# eVV_Driver_TMC5130.net
KiCad netlist of a schematic drawn in Altium Designer
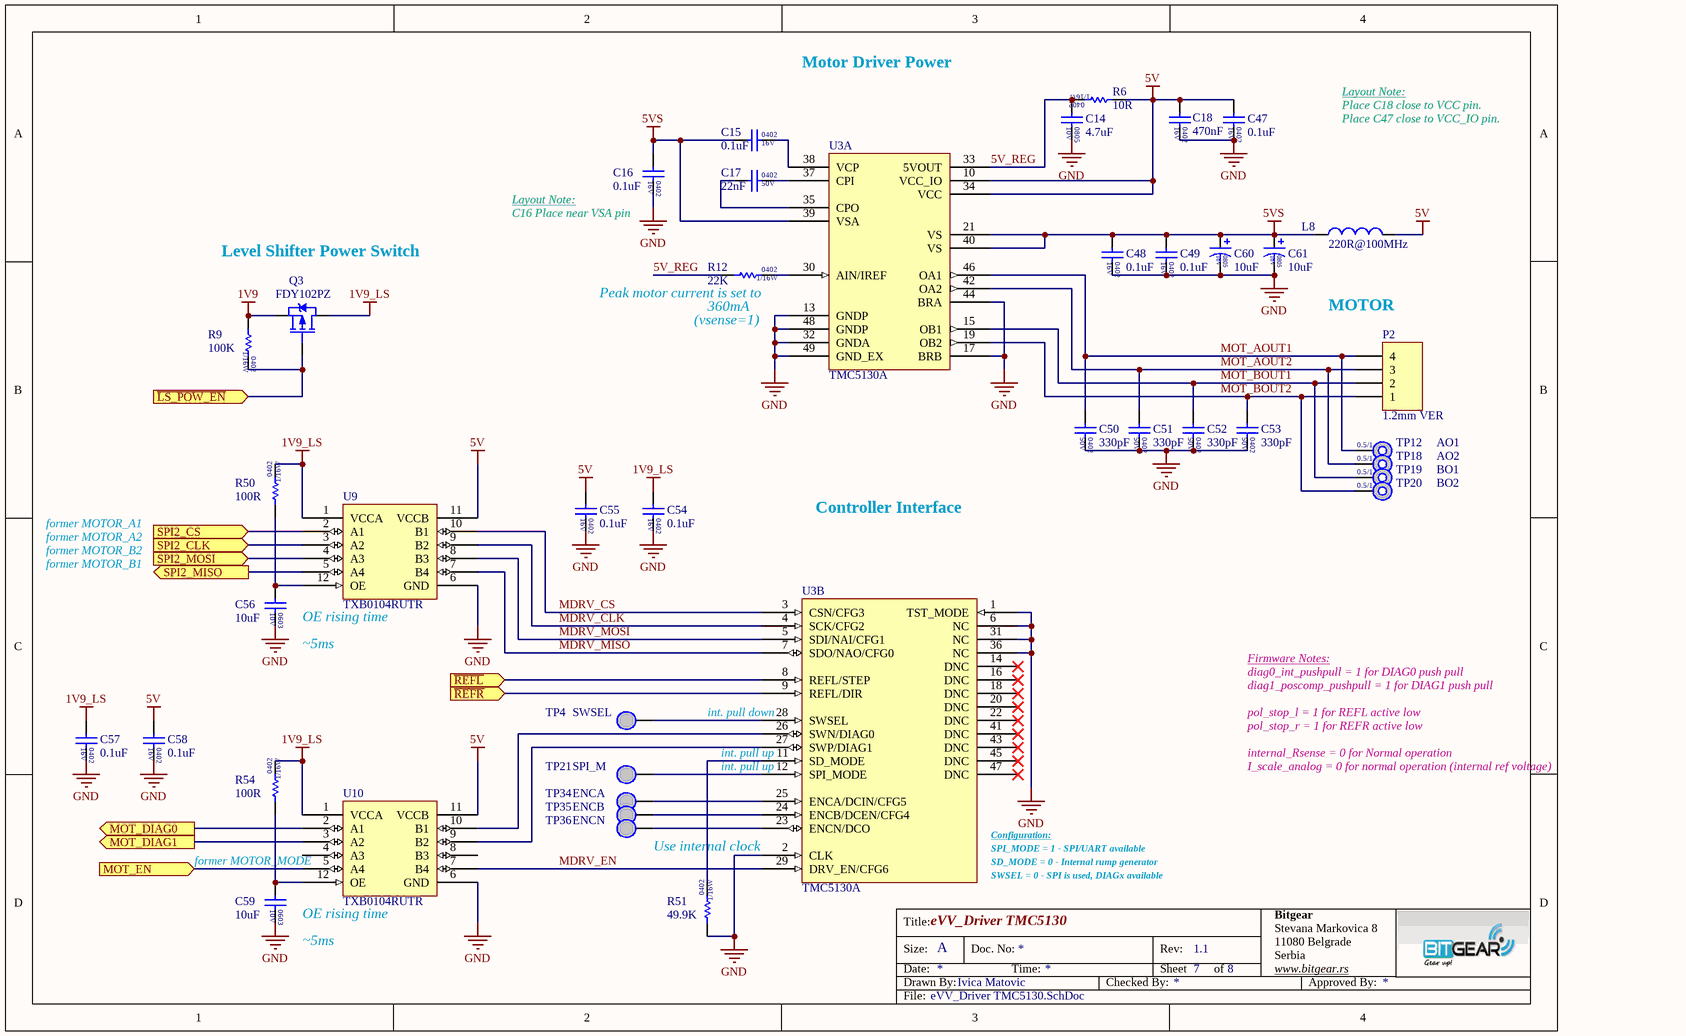
[diagram p0: eVV_Driver TMC5130.SchDoc]

(export (version "E")
  (design (tool "Eeschema 10.0.6"))
  (components
    (comp (ref "C14")
      (value "4.7uF")
      (footprint "CAPC2012X145N")
      (description "Capacitor Ceramic 4.7uF 2012 (0805) 10V X5R 10%")
      (fields (field (name "MANUFACTURER") "Samsung Electro-Mechanics America"))
      (libsource (lib "ecoVENTV") (part "Cap-2012 (0805) CER 4.7uF 10V X5R 10%"))
    )
    (comp (ref "C15")
      (value "0.1uF")
      (footprint "CAPC1005X60N")
      (description "CAP CER 0.1UF 0402 (1005) 16V X7R 10%")
      (fields (field (name "MANUFACTURER") "Murata Electronics North America"))
      (libsource (lib "ecoVENTV") (part "Cap-1005 (0402) CER 0.1UF 16V X7R 10%"))
    )
    (comp (ref "C16")
      (value "0.1uF")
      (footprint "CAPC1005X60N")
      (description "CAP CER 0.1UF 0402 (1005) 16V X7R 10%")
      (fields (field (name "MANUFACTURER") "Murata Electronics North America"))
      (libsource (lib "ecoVENTV") (part "Cap-1005 (0402) CER 0.1UF 16V X7R 10%"))
    )
    (comp (ref "C17")
      (value "22nF")
      (footprint "CAPC1005X60N")
      (description "Cap-1005 (0402) CER 22nF 50V X7R 10%")
      (fields (field (name "MANUFACTURER") "Murata Electronics North America"))
      (libsource (lib "ecoVENTV") (part "Cap-1005 (0402) CER 22nF 50V X7R 10%"))
    )
    (comp (ref "C18")
      (value "470nF")
      (footprint "CAPC1005X60N")
      (description "CAP Cer 470nF 0402 (1005) 16V X5R 10%")
      (fields (field (name "MANUFACTURER") "TDK"))
      (libsource (lib "ecoVENTV") (part "Cap-1005 (0402) Cer 470nF 16V X5R 10%"))
    )
    (comp (ref "C47")
      (value "0.1uF")
      (footprint "CAPC1005X60N")
      (description "CAP CER 0.1UF 0402 (1005) 16V X7R 10%")
      (fields (field (name "MANUFACTURER") "Murata Electronics North America"))
      (libsource (lib "ecoVENTV") (part "Cap-1005 (0402) CER 0.1UF 16V X7R 10%"))
    )
    (comp (ref "C48")
      (value "0.1uF")
      (footprint "CAPC1005X60N")
      (description "CAP CER 0.1UF 0402 (1005) 16V X7R 10%")
      (fields (field (name "MANUFACTURER") "Murata Electronics North America"))
      (libsource (lib "ecoVENTV") (part "Cap-1005 (0402) CER 0.1UF 16V X7R 10%"))
    )
    (comp (ref "C49")
      (value "0.1uF")
      (footprint "CAPC1005X60N")
      (description "CAP CER 0.1UF 0402 (1005) 16V X7R 10%")
      (fields (field (name "MANUFACTURER") "Murata Electronics North America"))
      (libsource (lib "ecoVENTV") (part "Cap-1005 (0402) CER 0.1UF 16V X7R 10%"))
    )
    (comp (ref "C50")
      (value "330pF")
      (footprint "CAPC1005X60N")
      (description "Cap-1005 (0402) CER 330pF 50V C0G 5%")
      (fields (field (name "MANUFACTURER") "Murata Electronics North America"))
      (libsource (lib "ecoVENTV") (part "Cap-1005 (0402) CER 330pF 50V C0G 5%"))
    )
    (comp (ref "C51")
      (value "330pF")
      (footprint "CAPC1005X60N")
      (description "Cap-1005 (0402) CER 330pF 50V C0G 5%")
      (fields (field (name "MANUFACTURER") "Murata Electronics North America"))
      (libsource (lib "ecoVENTV") (part "Cap-1005 (0402) CER 330pF 50V C0G 5%"))
    )
    (comp (ref "C52")
      (value "330pF")
      (footprint "CAPC1005X60N")
      (description "Cap-1005 (0402) CER 330pF 50V C0G 5%")
      (fields (field (name "MANUFACTURER") "Murata Electronics North America"))
      (libsource (lib "ecoVENTV") (part "Cap-1005 (0402) CER 330pF 50V C0G 5%"))
    )
    (comp (ref "C53")
      (value "330pF")
      (footprint "CAPC1005X60N")
      (description "Cap-1005 (0402) CER 330pF 50V C0G 5%")
      (fields (field (name "MANUFACTURER") "Murata Electronics North America"))
      (libsource (lib "ecoVENTV") (part "Cap-1005 (0402) CER 330pF 50V C0G 5%"))
    )
    (comp (ref "C54")
      (value "0.1uF")
      (footprint "CAPC1005X60N")
      (description "CAP CER 0.1UF 0402 (1005) 16V X7R 10%")
      (fields (field (name "MANUFACTURER") "Murata Electronics North America"))
      (libsource (lib "ecoVENTV") (part "Cap-1005 (0402) CER 0.1UF 16V X7R 10%"))
    )
    (comp (ref "C55")
      (value "0.1uF")
      (footprint "CAPC1005X60N")
      (description "CAP CER 0.1UF 0402 (1005) 16V X7R 10%")
      (fields (field (name "MANUFACTURER") "Murata Electronics North America"))
      (libsource (lib "ecoVENTV") (part "Cap-1005 (0402) CER 0.1UF 16V X7R 10%"))
    )
    (comp (ref "C56")
      (value "10uF")
      (footprint "CAPC1608X95N")
      (description "Capacitor Ceramic 10uF 1608 (0603) 10V X5R 20%")
      (fields (field (name "MANUFACTURER") "Taiyo Yuden"))
      (libsource (lib "ecoVENTV") (part "Cap-1608 (0603) CER 10uF 10V X5R 20%"))
    )
    (comp (ref "C57")
      (value "0.1uF")
      (footprint "CAPC1005X60N")
      (description "CAP CER 0.1UF 0402 (1005) 16V X7R 10%")
      (fields (field (name "MANUFACTURER") "Murata Electronics North America"))
      (libsource (lib "ecoVENTV") (part "Cap-1005 (0402) CER 0.1UF 16V X7R 10%"))
    )
    (comp (ref "C58")
      (value "0.1uF")
      (footprint "CAPC1005X60N")
      (description "CAP CER 0.1UF 0402 (1005) 16V X7R 10%")
      (fields (field (name "MANUFACTURER") "Murata Electronics North America"))
      (libsource (lib "ecoVENTV") (part "Cap-1005 (0402) CER 0.1UF 16V X7R 10%"))
    )
    (comp (ref "C59")
      (value "10uF")
      (footprint "CAPC1608X95N")
      (description "Capacitor Ceramic 10uF 1608 (0603) 10V X5R 20%")
      (fields (field (name "MANUFACTURER") "Taiyo Yuden"))
      (libsource (lib "ecoVENTV") (part "Cap-1608 (0603) CER 10uF 10V X5R 20%"))
    )
    (comp (ref "C60")
      (value "10uF")
      (footprint "CAPMP2012X120N")
      (description "Cap-2012 (0805) TAN 10uF 16V 20%")
      (fields (field (name "MANUFACTURER") "Rohm Semiconductor"))
      (libsource (lib "ecoVENTV") (part "Cap-2012 (0805) TAN 10uF 16V 20%"))
    )
    (comp (ref "C61")
      (value "10uF")
      (footprint "CAPMP2012X120N")
      (description "Cap-2012 (0805) TAN 10uF 16V 20%")
      (fields (field (name "MANUFACTURER") "Rohm Semiconductor"))
      (libsource (lib "ecoVENTV") (part "Cap-2012 (0805) TAN 10uF 16V 20%"))
    )
    (comp (ref "L8")
      (value "220R@100MHz")
      (footprint "INDC1005X60N")
      (description "FERRITE BEAD 220 Ohm 800mA 0402")
      (fields (field (name "MANUFACTURER") "Taiyo Yuden"))
      (libsource (lib "ecoVENTV") (part "FBead-1005 (0402) 220 Ohm 800mA"))
    )
    (comp (ref "P2")
      (value "1.2mm VER")
      (footprint "MOLEX_0781710004")
      (description "1.2mm pitch Pico-EZmate, Wire to Board, Vertical, with Locks, 1X4")
      (fields (field (name "MANUFACTURER") "Molex"))
      (libsource (lib "ecoVENTV") (part "Connector MOLEX Pico-EZmate 1X4 1.2mm"))
    )
    (comp (ref "Q3")
      (value "FDY102PZ")
      (footprint "SOT50P160X78-3N")
      (description "P-MOSFET Single 0.83A Low Vgs")
      (fields (field (name "MANUFACTURER") "Fairchild"))
      (libsource (lib "ecoVENTV") (part "FDY102PZ"))
    )
    (comp (ref "R6")
      (value "10R")
      (footprint "RESC1005X40AN")
      (description "Res-1005 (0402) 10 Ohm 1/16W 1%")
      (fields (field (name "MANUFACTURER") "Samsung Electro-Mechanics America"))
      (libsource (lib "ecoVENTV") (part "Res-1005 (0402) 10 Ohm 1/16W 1%"))
    )
    (comp (ref "R9")
      (value "100K")
      (footprint "RESC1005X40AN")
      (description "Res-1005 (0402) 100 KOhm 1/16W 1%")
      (fields (field (name "MANUFACTURER") "Vishay Dale"))
      (libsource (lib "ecoVENTV") (part "Res-1005 (0402) 100 KOhm 1/16W 1%"))
    )
    (comp (ref "R12")
      (value "22K")
      (footprint "RESC1005X40AN")
      (description "Res-1005 (0402) 22 KOhm 1/16W 1%")
      (fields (field (name "MANUFACTURER") "Yageo"))
      (libsource (lib "ecoVENTV") (part "Res-1005 (0402) 22 KOhm 1/16W 1%"))
    )
    (comp (ref "R50")
      (value "100R")
      (footprint "RESC1005X40AN")
      (description "Res-1005 (0402) 100 Ohm 1/16W 1%")
      (fields (field (name "MANUFACTURER") "Vishay Dale"))
      (libsource (lib "ecoVENTV") (part "Res-1005 (0402) 100 Ohm 1/16W 1%"))
    )
    (comp (ref "R51")
      (value "49.9K")
      (footprint "RESC1005X40AN")
      (description "Res-1005 (0402) 49.9 KOhm 1/16W 1%")
      (fields (field (name "MANUFACTURER") "Yageo"))
      (libsource (lib "ecoVENTV") (part "Res-1005 (0402) 49.9 KOhm 1/16W 1%"))
    )
    (comp (ref "R54")
      (value "100R")
      (footprint "RESC1005X40AN")
      (description "Res-1005 (0402) 100 Ohm 1/16W 1%")
      (fields (field (name "MANUFACTURER") "Vishay Dale"))
      (libsource (lib "ecoVENTV") (part "Res-1005 (0402) 100 Ohm 1/16W 1%"))
    )
    (comp (ref "TP4")
      (value "SWSEL")
      (footprint "TEST_POINT_1MM")
      (description "Test point")
      (libsource (lib "ecoVENTV") (part "TP"))
    )
    (comp (ref "TP12")
      (value "AO1")
      (footprint "TEST_POINT_TH_1MM")
      (description "Test point Through Hole")
      (libsource (lib "ecoVENTV") (part "TP TH"))
    )
    (comp (ref "TP18")
      (value "AO2")
      (footprint "TEST_POINT_TH_1MM")
      (description "Test point Through Hole")
      (libsource (lib "ecoVENTV") (part "TP TH"))
    )
    (comp (ref "TP19")
      (value "BO1")
      (footprint "TEST_POINT_TH_1MM")
      (description "Test point Through Hole")
      (libsource (lib "ecoVENTV") (part "TP TH"))
    )
    (comp (ref "TP20")
      (value "BO2")
      (footprint "TEST_POINT_TH_1MM")
      (description "Test point Through Hole")
      (libsource (lib "ecoVENTV") (part "TP TH"))
    )
    (comp (ref "TP21")
      (value "SPI_M")
      (footprint "TEST_POINT_1MM")
      (description "Test point")
      (libsource (lib "ecoVENTV") (part "TP"))
    )
    (comp (ref "TP34")
      (value "ENCA")
      (footprint "TEST_POINT_1MM")
      (description "Test point")
      (libsource (lib "ecoVENTV") (part "TP"))
    )
    (comp (ref "TP35")
      (value "ENCB")
      (footprint "TEST_POINT_1MM")
      (description "Test point")
      (libsource (lib "ecoVENTV") (part "TP"))
    )
    (comp (ref "TP36")
      (value "ENCN")
      (footprint "TEST_POINT_1MM")
      (description "Test point")
      (libsource (lib "ecoVENTV") (part "TP"))
    )
    (comp (ref "U3")
      (value "TMC5130A")
      (footprint "QFP50P900X900X120-48N-TP")
      (description "Universal high voltage controller/driver for two-phase bipolar stepper motor")
      (fields (field (name "MANUFACTURER") "Trinamic Motion Control"))
      (libsource (lib "ecoVENTV") (part "TMC5130A"))
    )
    (comp (ref "U9")
      (value "TXB0104RUTR")
      (footprint "RUT40P170X200X55-12N")
      (description "4-bit Bidirectional Voltage Translator")
      (fields (field (name "MANUFACTURER") "Texas Instruments"))
      (libsource (lib "ecoVENTV") (part "TXB0104RUTR"))
    )
    (comp (ref "U10")
      (value "TXB0104RUTR")
      (footprint "RUT40P170X200X55-12N")
      (description "4-bit Bidirectional Voltage Translator")
      (fields (field (name "MANUFACTURER") "Texas Instruments"))
      (libsource (lib "ecoVENTV") (part "TXB0104RUTR"))
    )
  )
  (nets
    (net (code "1") (name "/5V_REG") (class "Default")
      (node (ref "C14") (pin "1") (pinfunction "1_1") (pintype "passive"))
      (node (ref "R12") (pin "2") (pinfunction "2_2") (pintype "passive"))
      (node (ref "R6") (pin "1") (pinfunction "1_1") (pintype "passive"))
      (node (ref "U3") (pin "33") (pinfunction "5VOUT_33") (pintype "power_in"))
    )
    (net (code "2") (name "/LS_POW_EN") (class "Default")
      (node (ref "Q3") (pin "1") (pinfunction "G_1") (pintype "passive"))
      (node (ref "R9") (pin "1") (pinfunction "1_1") (pintype "passive"))
    )
    (net (code "3") (name "/MDRV_CLK") (class "Default")
      (node (ref "U3") (pin "4") (pinfunction "SCK/CFG2_4") (pintype "input"))
      (node (ref "U9") (pin "9") (pinfunction "B2_9") (pintype "bidirectional"))
    )
    (net (code "4") (name "/MDRV_CS") (class "Default")
      (node (ref "U3") (pin "3") (pinfunction "CSN/CFG3_3") (pintype "input"))
      (node (ref "U9") (pin "10") (pinfunction "B1_10") (pintype "bidirectional"))
    )
    (net (code "5") (name "/MDRV_EN") (class "Default")
      (node (ref "U10") (pin "7") (pinfunction "B4_7") (pintype "bidirectional"))
      (node (ref "U3") (pin "29") (pinfunction "DRV_EN/CFG6_29") (pintype "input"))
    )
    (net (code "6") (name "/MDRV_MISO") (class "Default")
      (node (ref "U3") (pin "7") (pinfunction "SDO/NAO/CFG0_7") (pintype "bidirectional"))
      (node (ref "U9") (pin "7") (pinfunction "B4_7") (pintype "bidirectional"))
    )
    (net (code "7") (name "/MDRV_MOSI") (class "Default")
      (node (ref "U3") (pin "5") (pinfunction "SDI/NAI/CFG1_5") (pintype "input"))
      (node (ref "U9") (pin "8") (pinfunction "B3_8") (pintype "bidirectional"))
    )
    (net (code "8") (name "/MOT_AOUT1") (class "Default")
      (node (ref "C50") (pin "1") (pinfunction "1_1") (pintype "passive"))
      (node (ref "P2") (pin "4") (pinfunction "4_4") (pintype "passive"))
      (node (ref "TP12") (pin "1") (pinfunction "1_1") (pintype "passive"))
      (node (ref "U3") (pin "46") (pinfunction "OA1_46") (pintype "output"))
    )
    (net (code "9") (name "/MOT_AOUT2") (class "Default")
      (node (ref "C51") (pin "1") (pinfunction "1_1") (pintype "passive"))
      (node (ref "P2") (pin "3") (pinfunction "3_3") (pintype "passive"))
      (node (ref "TP18") (pin "1") (pinfunction "1_1") (pintype "passive"))
      (node (ref "U3") (pin "42") (pinfunction "OA2_42") (pintype "output"))
    )
    (net (code "10") (name "/MOT_BOUT1") (class "Default")
      (node (ref "C52") (pin "1") (pinfunction "1_1") (pintype "passive"))
      (node (ref "P2") (pin "2") (pinfunction "2_2") (pintype "passive"))
      (node (ref "TP19") (pin "1") (pinfunction "1_1") (pintype "passive"))
      (node (ref "U3") (pin "15") (pinfunction "OB1_15") (pintype "output"))
    )
    (net (code "11") (name "/MOT_BOUT2") (class "Default")
      (node (ref "C53") (pin "1") (pinfunction "1_1") (pintype "passive"))
      (node (ref "P2") (pin "1") (pinfunction "1_1") (pintype "passive"))
      (node (ref "TP20") (pin "1") (pinfunction "1_1") (pintype "passive"))
      (node (ref "U3") (pin "19") (pinfunction "OB2_19") (pintype "output"))
    )
    (net (code "12") (name "/MOT_DIAG0") (class "Default")
      (node (ref "U10") (pin "2") (pinfunction "A1_2") (pintype "bidirectional"))
    )
    (net (code "13") (name "/MOT_DIAG1") (class "Default")
      (node (ref "U10") (pin "3") (pinfunction "A2_3") (pintype "bidirectional"))
    )
    (net (code "14") (name "/MOT_EN") (class "Default")
      (node (ref "U10") (pin "5") (pinfunction "A4_5") (pintype "bidirectional"))
    )
    (net (code "15") (name "/REFL") (class "Default")
      (node (ref "U3") (pin "8") (pinfunction "REFL/STEP_8") (pintype "input"))
    )
    (net (code "16") (name "/REFR") (class "Default")
      (node (ref "U3") (pin "9") (pinfunction "REFL/DIR_9") (pintype "input"))
    )
    (net (code "17") (name "/SPI2_CLK") (class "Default")
      (node (ref "U9") (pin "3") (pinfunction "A2_3") (pintype "bidirectional"))
    )
    (net (code "18") (name "/SPI2_CS") (class "Default")
      (node (ref "U9") (pin "2") (pinfunction "A1_2") (pintype "bidirectional"))
    )
    (net (code "19") (name "/SPI2_MISO") (class "Default")
      (node (ref "U9") (pin "5") (pinfunction "A4_5") (pintype "bidirectional"))
    )
    (net (code "20") (name "/SPI2_MOSI") (class "Default")
      (node (ref "U9") (pin "4") (pinfunction "A3_4") (pintype "bidirectional"))
    )
    (net (code "21") (name "1V9") (class "Default")
      (node (ref "Q3") (pin "2") (pinfunction "S_2") (pintype "passive"))
      (node (ref "R9") (pin "2") (pinfunction "2_2") (pintype "passive"))
    )
    (net (code "22") (name "1V9_LS") (class "Default")
      (node (ref "C54") (pin "1") (pinfunction "1_1") (pintype "passive"))
      (node (ref "C57") (pin "1") (pinfunction "1_1") (pintype "passive"))
      (node (ref "Q3") (pin "3") (pinfunction "D_3") (pintype "passive"))
      (node (ref "R50") (pin "1") (pinfunction "1_1") (pintype "passive"))
      (node (ref "R54") (pin "1") (pinfunction "1_1") (pintype "passive"))
      (node (ref "U10") (pin "1") (pinfunction "VCCA_1") (pintype "power_in"))
      (node (ref "U9") (pin "1") (pinfunction "VCCA_1") (pintype "power_in"))
    )
    (net (code "23") (name "5V") (class "Default")
      (node (ref "C18") (pin "1") (pinfunction "1_1") (pintype "passive"))
      (node (ref "C47") (pin "1") (pinfunction "1_1") (pintype "passive"))
      (node (ref "C55") (pin "1") (pinfunction "1_1") (pintype "passive"))
      (node (ref "C58") (pin "1") (pinfunction "1_1") (pintype "passive"))
      (node (ref "L8") (pin "2") (pinfunction "2_2") (pintype "passive"))
      (node (ref "R6") (pin "2") (pinfunction "2_2") (pintype "passive"))
      (node (ref "U10") (pin "11") (pinfunction "VCCB_11") (pintype "power_in"))
      (node (ref "U3") (pin "10") (pinfunction "VCC_IO_10") (pintype "power_in"))
      (node (ref "U3") (pin "34") (pinfunction "VCC_34") (pintype "power_in"))
      (node (ref "U9") (pin "11") (pinfunction "VCCB_11") (pintype "power_in"))
    )
    (net (code "24") (name "5VS") (class "Default")
      (node (ref "C15") (pin "1") (pinfunction "1_1") (pintype "passive"))
      (node (ref "C16") (pin "1") (pinfunction "1_1") (pintype "passive"))
      (node (ref "C48") (pin "1") (pinfunction "1_1") (pintype "passive"))
      (node (ref "C49") (pin "1") (pinfunction "1_1") (pintype "passive"))
      (node (ref "C60") (pin "1") (pinfunction "1_1") (pintype "passive"))
      (node (ref "C61") (pin "1") (pinfunction "1_1") (pintype "passive"))
      (node (ref "L8") (pin "1") (pinfunction "1_1") (pintype "passive"))
      (node (ref "U3") (pin "21") (pinfunction "VS_21") (pintype "power_in"))
      (node (ref "U3") (pin "39") (pinfunction "VSA_39") (pintype "power_in"))
      (node (ref "U3") (pin "40") (pinfunction "VS_40") (pintype "power_in"))
    )
    (net (code "25") (name "GND") (class "Default")
      (node (ref "C14") (pin "2") (pinfunction "2_2") (pintype "passive"))
      (node (ref "C16") (pin "2") (pinfunction "2_2") (pintype "passive"))
      (node (ref "C18") (pin "2") (pinfunction "2_2") (pintype "passive"))
      (node (ref "C47") (pin "2") (pinfunction "2_2") (pintype "passive"))
      (node (ref "C48") (pin "2") (pinfunction "2_2") (pintype "passive"))
      (node (ref "C49") (pin "2") (pinfunction "2_2") (pintype "passive"))
      (node (ref "C50") (pin "2") (pinfunction "2_2") (pintype "passive"))
      (node (ref "C51") (pin "2") (pinfunction "2_2") (pintype "passive"))
      (node (ref "C52") (pin "2") (pinfunction "2_2") (pintype "passive"))
      (node (ref "C53") (pin "2") (pinfunction "2_2") (pintype "passive"))
      (node (ref "C54") (pin "2") (pinfunction "2_2") (pintype "passive"))
      (node (ref "C55") (pin "2") (pinfunction "2_2") (pintype "passive"))
      (node (ref "C56") (pin "2") (pinfunction "2_2") (pintype "passive"))
      (node (ref "C57") (pin "2") (pinfunction "2_2") (pintype "passive"))
      (node (ref "C58") (pin "2") (pinfunction "2_2") (pintype "passive"))
      (node (ref "C59") (pin "2") (pinfunction "2_2") (pintype "passive"))
      (node (ref "C60") (pin "2") (pinfunction "2_2") (pintype "passive"))
      (node (ref "C61") (pin "2") (pinfunction "2_2") (pintype "passive"))
      (node (ref "R51") (pin "2") (pinfunction "2_2") (pintype "passive"))
      (node (ref "U10") (pin "6") (pinfunction "GND_6") (pintype "power_in"))
      (node (ref "U3") (pin "1") (pinfunction "TST_MODE_1") (pintype "input"))
      (node (ref "U3") (pin "13") (pinfunction "GNDP_13") (pintype "power_in"))
      (node (ref "U3") (pin "17") (pinfunction "BRB_17") (pintype "passive"))
      (node (ref "U3") (pin "2") (pinfunction "CLK_2") (pintype "input"))
      (node (ref "U3") (pin "31") (pinfunction "NC_31") (pintype "passive"))
      (node (ref "U3") (pin "32") (pinfunction "GNDA_32") (pintype "power_in"))
      (node (ref "U3") (pin "36") (pinfunction "NC_36") (pintype "passive"))
      (node (ref "U3") (pin "44") (pinfunction "BRA_44") (pintype "passive"))
      (node (ref "U3") (pin "48") (pinfunction "GNDP_48") (pintype "power_in"))
      (node (ref "U3") (pin "49") (pinfunction "GND_EX_49") (pintype "power_in"))
      (node (ref "U3") (pin "6") (pinfunction "NC_6") (pintype "passive"))
      (node (ref "U9") (pin "6") (pinfunction "GND_6") (pintype "power_in"))
    )
    (net (code "26") (name "Net-(U3A-AIN{slash}IREF)") (class "Default")
      (node (ref "R12") (pin "1") (pinfunction "1_1") (pintype "passive"))
      (node (ref "U3") (pin "30") (pinfunction "AIN/IREF_30") (pintype "input"))
    )
    (net (code "27") (name "Net-(U3A-CPI)") (class "Default")
      (node (ref "C17") (pin "2") (pinfunction "2_2") (pintype "passive"))
      (node (ref "U3") (pin "37") (pinfunction "CPI_37") (pintype "passive"))
    )
    (net (code "28") (name "Net-(U3A-CPO)") (class "Default")
      (node (ref "C17") (pin "1") (pinfunction "1_1") (pintype "passive"))
      (node (ref "U3") (pin "35") (pinfunction "CPO_35") (pintype "passive"))
    )
    (net (code "29") (name "Net-(U3A-VCP)") (class "Default")
      (node (ref "C15") (pin "2") (pinfunction "2_2") (pintype "passive"))
      (node (ref "U3") (pin "38") (pinfunction "VCP_38") (pintype "passive"))
    )
    (net (code "30") (name "Net-(U3B-ENCA{slash}DCIN{slash}CFG5)") (class "Default")
      (node (ref "TP34") (pin "1") (pinfunction "1_1") (pintype "passive"))
      (node (ref "U3") (pin "25") (pinfunction "ENCA/DCIN/CFG5_25") (pintype "input"))
    )
    (net (code "31") (name "Net-(U3B-ENCB{slash}DCEN{slash}CFG4)") (class "Default")
      (node (ref "TP35") (pin "1") (pinfunction "1_1") (pintype "passive"))
      (node (ref "U3") (pin "24") (pinfunction "ENCB/DCEN/CFG4_24") (pintype "input"))
    )
    (net (code "32") (name "Net-(U3B-ENCN{slash}DCO)") (class "Default")
      (node (ref "TP36") (pin "1") (pinfunction "1_1") (pintype "passive"))
      (node (ref "U3") (pin "23") (pinfunction "ENCN/DCO_23") (pintype "bidirectional"))
    )
    (net (code "33") (name "Net-(U3B-SD_MODE)") (class "Default")
      (node (ref "R51") (pin "1") (pinfunction "1_1") (pintype "passive"))
      (node (ref "U3") (pin "11") (pinfunction "SD_MODE_11") (pintype "input"))
    )
    (net (code "34") (name "Net-(U3B-SPI_MODE)") (class "Default")
      (node (ref "TP21") (pin "1") (pinfunction "1_1") (pintype "passive"))
      (node (ref "U3") (pin "12") (pinfunction "SPI_MODE_12") (pintype "input"))
    )
    (net (code "35") (name "Net-(U3B-SWSEL)") (class "Default")
      (node (ref "TP4") (pin "1") (pinfunction "1_1") (pintype "passive"))
      (node (ref "U3") (pin "28") (pinfunction "SWSEL_28") (pintype "input"))
    )
    (net (code "36") (name "Net-(U9-OE)") (class "Default")
      (node (ref "C56") (pin "1") (pinfunction "1_1") (pintype "passive"))
      (node (ref "R50") (pin "2") (pinfunction "2_2") (pintype "passive"))
      (node (ref "U9") (pin "12") (pinfunction "OE_12") (pintype "input"))
    )
    (net (code "37") (name "Net-(U10-B1)") (class "Default")
      (node (ref "U10") (pin "10") (pinfunction "B1_10") (pintype "bidirectional"))
      (node (ref "U3") (pin "26") (pinfunction "SWN/DIAG0_26") (pintype "bidirectional"))
    )
    (net (code "38") (name "Net-(U10-B2)") (class "Default")
      (node (ref "U10") (pin "9") (pinfunction "B2_9") (pintype "bidirectional"))
      (node (ref "U3") (pin "27") (pinfunction "SWP/DIAG1_27") (pintype "bidirectional"))
    )
    (net (code "39") (name "Net-(U10-OE)") (class "Default")
      (node (ref "C59") (pin "1") (pinfunction "1_1") (pintype "passive"))
      (node (ref "R54") (pin "2") (pinfunction "2_2") (pintype "passive"))
      (node (ref "U10") (pin "12") (pinfunction "OE_12") (pintype "input"))
    )
    (net (code "40") (name "unconnected-(U3B-DNC-Pad14)") (class "Default")
      (node (ref "U3") (pin "14") (pinfunction "DNC_14") (pintype "passive+no_connect"))
    )
    (net (code "41") (name "unconnected-(U3B-DNC-Pad16)") (class "Default")
      (node (ref "U3") (pin "16") (pinfunction "DNC_16") (pintype "passive+no_connect"))
    )
    (net (code "42") (name "unconnected-(U3B-DNC-Pad18)") (class "Default")
      (node (ref "U3") (pin "18") (pinfunction "DNC_18") (pintype "passive+no_connect"))
    )
    (net (code "43") (name "unconnected-(U3B-DNC-Pad20)") (class "Default")
      (node (ref "U3") (pin "20") (pinfunction "DNC_20") (pintype "passive+no_connect"))
    )
    (net (code "44") (name "unconnected-(U3B-DNC-Pad22)") (class "Default")
      (node (ref "U3") (pin "22") (pinfunction "DNC_22") (pintype "passive+no_connect"))
    )
    (net (code "45") (name "unconnected-(U3B-DNC-Pad41)") (class "Default")
      (node (ref "U3") (pin "41") (pinfunction "DNC_41") (pintype "passive+no_connect"))
    )
    (net (code "46") (name "unconnected-(U3B-DNC-Pad43)") (class "Default")
      (node (ref "U3") (pin "43") (pinfunction "DNC_43") (pintype "passive+no_connect"))
    )
    (net (code "47") (name "unconnected-(U3B-DNC-Pad45)") (class "Default")
      (node (ref "U3") (pin "45") (pinfunction "DNC_45") (pintype "passive+no_connect"))
    )
    (net (code "48") (name "unconnected-(U3B-DNC-Pad47)") (class "Default")
      (node (ref "U3") (pin "47") (pinfunction "DNC_47") (pintype "passive+no_connect"))
    )
    (net (code "49") (name "unconnected-(U10-A3-Pad4)") (class "Default")
      (node (ref "U10") (pin "4") (pinfunction "A3_4") (pintype "bidirectional"))
    )
    (net (code "50") (name "unconnected-(U10-B3-Pad8)") (class "Default")
      (node (ref "U10") (pin "8") (pinfunction "B3_8") (pintype "bidirectional"))
    )
  )
)
